# relay-set-d-latch.net
KiCad netlist of a schematic drawn in EAGLE
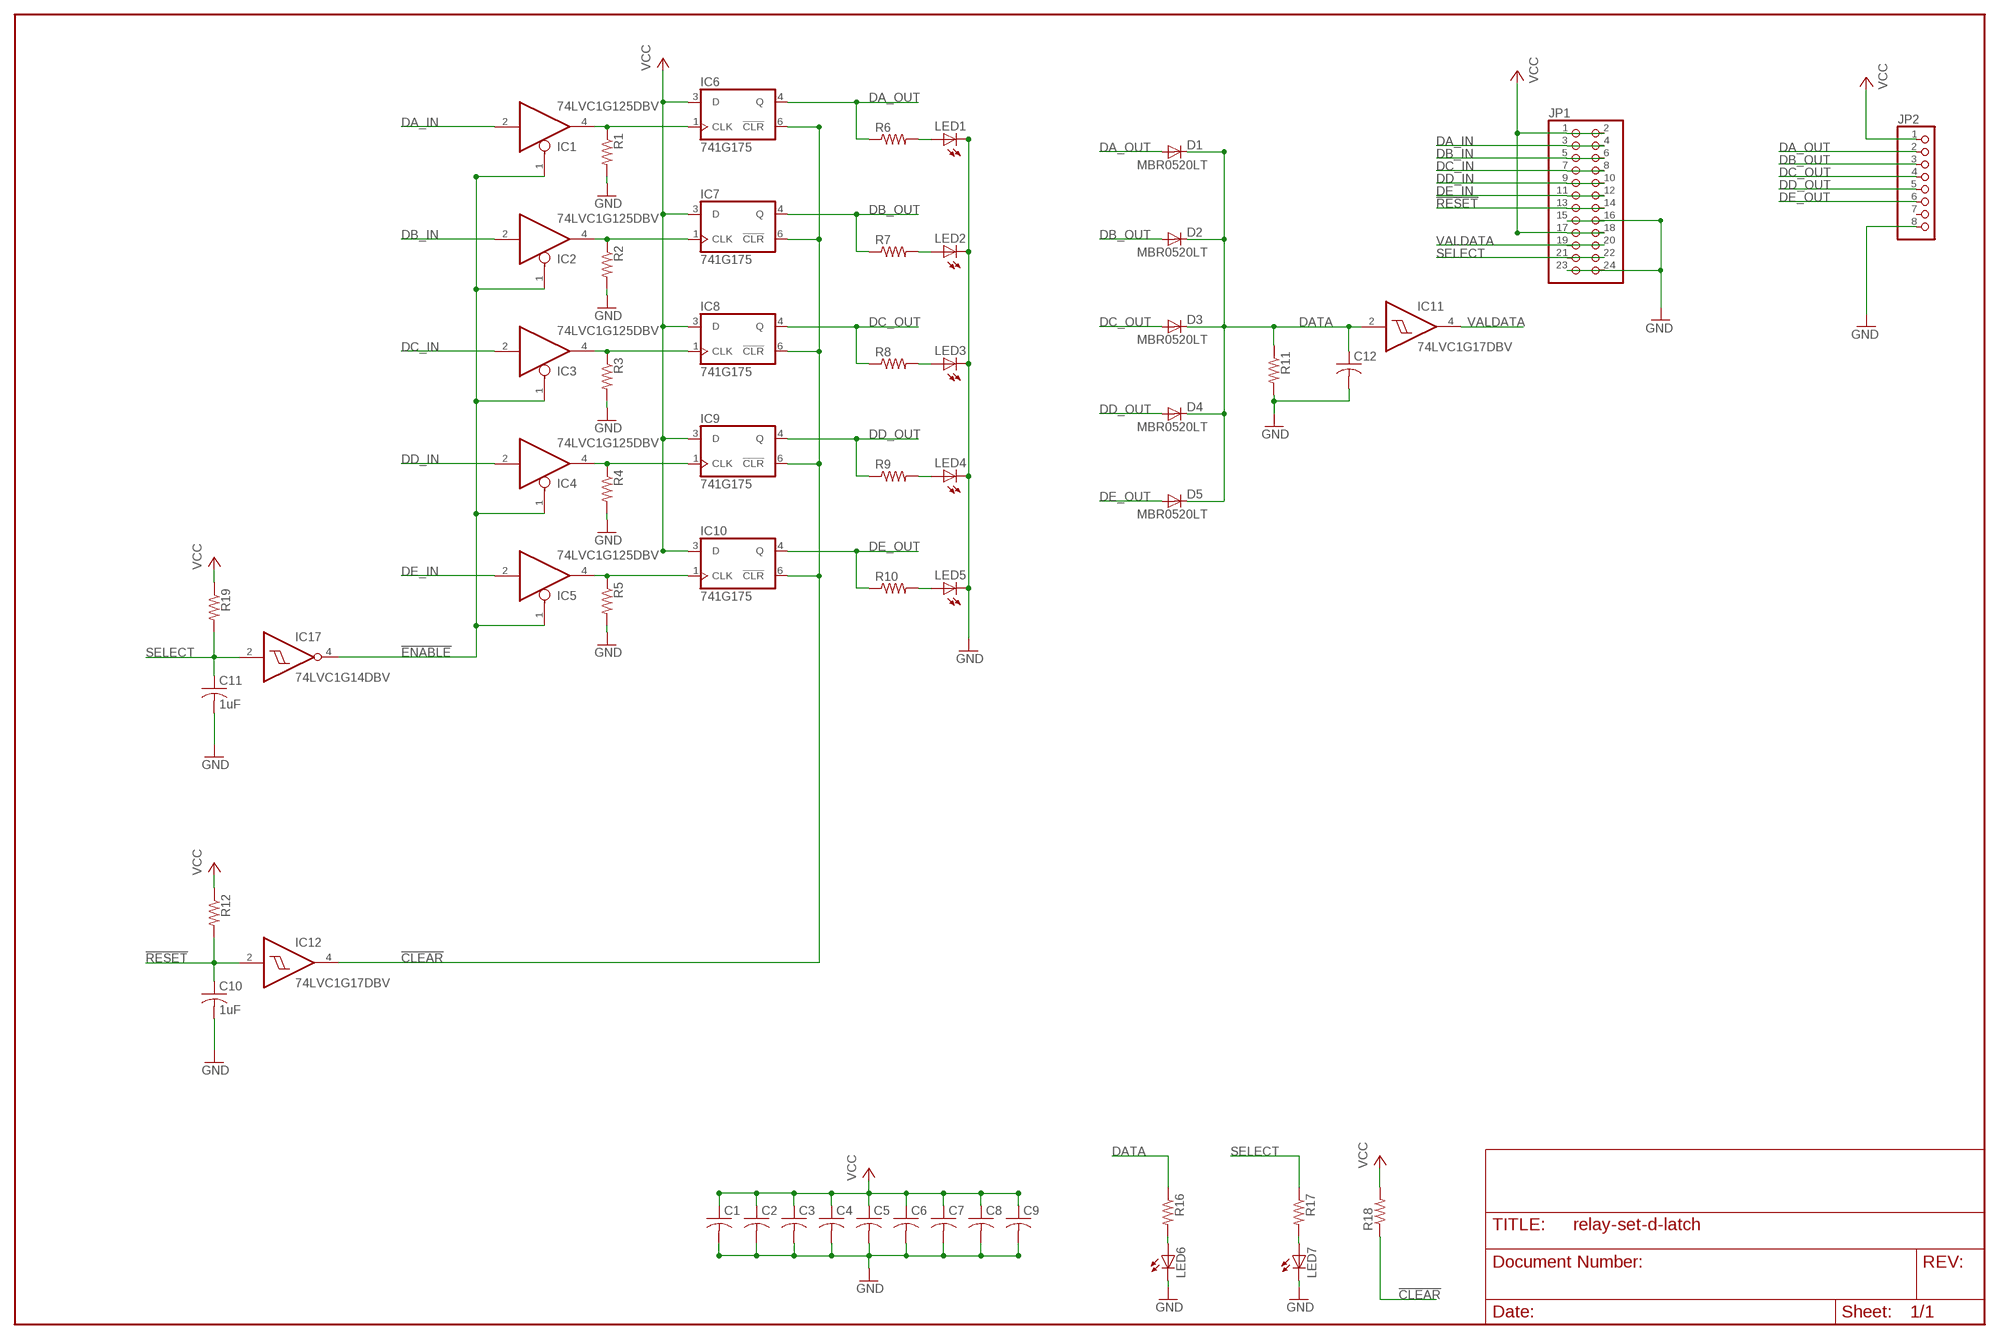
[diagram p0: schematic, sheet 1]

(export (version "E")
  (design (tool "Eeschema 10.0.6"))
  (components
    (comp (ref "C1")
      (value "C-USC0805")
      (footprint "eagle-import:C0805")
      (libsource (lib "eagle-import") (part "C-USC0805"))
    )
    (comp (ref "C2")
      (value "C-USC0805")
      (footprint "eagle-import:C0805")
      (libsource (lib "eagle-import") (part "C-USC0805"))
    )
    (comp (ref "C3")
      (value "C-USC0805")
      (footprint "eagle-import:C0805")
      (libsource (lib "eagle-import") (part "C-USC0805"))
    )
    (comp (ref "C4")
      (value "C-USC0805")
      (footprint "eagle-import:C0805")
      (libsource (lib "eagle-import") (part "C-USC0805"))
    )
    (comp (ref "C5")
      (value "C-USC0603K")
      (footprint "eagle-import:C0603K")
      (libsource (lib "eagle-import") (part "C-USC0603K"))
    )
    (comp (ref "C6")
      (value "C-USC0603K")
      (footprint "eagle-import:C0603K")
      (libsource (lib "eagle-import") (part "C-USC0603K"))
    )
    (comp (ref "C7")
      (value "C-USC0603K")
      (footprint "eagle-import:C0603K")
      (libsource (lib "eagle-import") (part "C-USC0603K"))
    )
    (comp (ref "C8")
      (value "C-USC0603K")
      (footprint "eagle-import:C0603K")
      (libsource (lib "eagle-import") (part "C-USC0603K"))
    )
    (comp (ref "C9")
      (value "C-USC0603K")
      (footprint "eagle-import:C0603K")
      (libsource (lib "eagle-import") (part "C-USC0603K"))
    )
    (comp (ref "C10")
      (value "1uF")
      (footprint "eagle-import:C0603K")
      (libsource (lib "eagle-import") (part "C-USC0603K"))
    )
    (comp (ref "C11")
      (value "1uF")
      (footprint "eagle-import:C0603K")
      (libsource (lib "eagle-import") (part "C-USC0603K"))
    )
    (comp (ref "C12")
      (value "C-USC0805")
      (footprint "eagle-import:C0805")
      (libsource (lib "eagle-import") (part "C-USC0805"))
    )
    (comp (ref "D1")
      (value "MBR0520LT")
      (footprint "eagle-import:SOD123")
      (libsource (lib "eagle-import") (part "MBR0520LT"))
    )
    (comp (ref "D2")
      (value "MBR0520LT")
      (footprint "eagle-import:SOD123")
      (libsource (lib "eagle-import") (part "MBR0520LT"))
    )
    (comp (ref "D3")
      (value "MBR0520LT")
      (footprint "eagle-import:SOD123")
      (libsource (lib "eagle-import") (part "MBR0520LT"))
    )
    (comp (ref "D4")
      (value "MBR0520LT")
      (footprint "eagle-import:SOD123")
      (libsource (lib "eagle-import") (part "MBR0520LT"))
    )
    (comp (ref "D5")
      (value "MBR0520LT")
      (footprint "eagle-import:SOD123")
      (libsource (lib "eagle-import") (part "MBR0520LT"))
    )
    (comp (ref "IC1")
      (value "74LVC1G125DBV")
      (footprint "eagle-import:SOT23-5")
      (libsource (lib "eagle-import") (part "741G125DBVLVC"))
    )
    (comp (ref "IC2")
      (value "74LVC1G125DBV")
      (footprint "eagle-import:SOT23-5")
      (libsource (lib "eagle-import") (part "741G125DBVLVC"))
    )
    (comp (ref "IC3")
      (value "74LVC1G125DBV")
      (footprint "eagle-import:SOT23-5")
      (libsource (lib "eagle-import") (part "741G125DBVLVC"))
    )
    (comp (ref "IC4")
      (value "74LVC1G125DBV")
      (footprint "eagle-import:SOT23-5")
      (libsource (lib "eagle-import") (part "741G125DBVLVC"))
    )
    (comp (ref "IC5")
      (value "74LVC1G125DBV")
      (footprint "eagle-import:SOT23-5")
      (libsource (lib "eagle-import") (part "741G125DBVLVC"))
    )
    (comp (ref "IC6")
      (value "741G175")
      (footprint "eagle-import:DBV_R-PDSO-G6")
      (libsource (lib "eagle-import") (part "741G175"))
    )
    (comp (ref "IC7")
      (value "741G175")
      (footprint "eagle-import:DBV_R-PDSO-G6")
      (libsource (lib "eagle-import") (part "741G175"))
    )
    (comp (ref "IC8")
      (value "741G175")
      (footprint "eagle-import:DBV_R-PDSO-G6")
      (libsource (lib "eagle-import") (part "741G175"))
    )
    (comp (ref "IC9")
      (value "741G175")
      (footprint "eagle-import:DBV_R-PDSO-G6")
      (libsource (lib "eagle-import") (part "741G175"))
    )
    (comp (ref "IC10")
      (value "741G175")
      (footprint "eagle-import:DBV_R-PDSO-G6")
      (libsource (lib "eagle-import") (part "741G175"))
    )
    (comp (ref "IC11")
      (value "74LVC1G17DBV")
      (footprint "eagle-import:SOT23-5")
      (libsource (lib "eagle-import") (part "741G17DBVLVC"))
    )
    (comp (ref "IC12")
      (value "74LVC1G17DBV")
      (footprint "eagle-import:SOT23-5")
      (libsource (lib "eagle-import") (part "741G17DBVLVC"))
    )
    (comp (ref "IC17")
      (value "74LVC1G14DBV")
      (footprint "eagle-import:SOT23-5")
      (libsource (lib "eagle-import") (part "741G14DBVLVC"))
    )
    (comp (ref "JP1")
      (value "PINHD-2X12")
      (footprint "eagle-import:2X12")
      (libsource (lib "eagle-import") (part "PINHD-2X12"))
    )
    (comp (ref "JP2")
      (value "PINHD-1X8")
      (footprint "eagle-import:1X08")
      (libsource (lib "eagle-import") (part "PINHD-1X8"))
    )
    (comp (ref "LED1")
      (value "LEDCHIP-LED0805")
      (footprint "eagle-import:CHIP-LED0805")
      (libsource (lib "eagle-import") (part "LEDCHIP-LED0805"))
    )
    (comp (ref "LED2")
      (value "LEDCHIP-LED0805")
      (footprint "eagle-import:CHIP-LED0805")
      (libsource (lib "eagle-import") (part "LEDCHIP-LED0805"))
    )
    (comp (ref "LED3")
      (value "LEDCHIP-LED0805")
      (footprint "eagle-import:CHIP-LED0805")
      (libsource (lib "eagle-import") (part "LEDCHIP-LED0805"))
    )
    (comp (ref "LED4")
      (value "LEDCHIP-LED0805")
      (footprint "eagle-import:CHIP-LED0805")
      (libsource (lib "eagle-import") (part "LEDCHIP-LED0805"))
    )
    (comp (ref "LED5")
      (value "LEDCHIP-LED0805")
      (footprint "eagle-import:CHIP-LED0805")
      (libsource (lib "eagle-import") (part "LEDCHIP-LED0805"))
    )
    (comp (ref "LED6")
      (value "LEDCHIP-LED0805")
      (footprint "eagle-import:CHIP-LED0805")
      (libsource (lib "eagle-import") (part "LEDCHIP-LED0805"))
    )
    (comp (ref "LED7")
      (value "LEDCHIP-LED0805")
      (footprint "eagle-import:CHIP-LED0805")
      (libsource (lib "eagle-import") (part "LEDCHIP-LED0805"))
    )
    (comp (ref "R1")
      (value "R-US_R0805")
      (footprint "eagle-import:R0805")
      (libsource (lib "eagle-import") (part "R-US_R0805"))
    )
    (comp (ref "R2")
      (value "R-US_R0805")
      (footprint "eagle-import:R0805")
      (libsource (lib "eagle-import") (part "R-US_R0805"))
    )
    (comp (ref "R3")
      (value "R-US_R0805")
      (footprint "eagle-import:R0805")
      (libsource (lib "eagle-import") (part "R-US_R0805"))
    )
    (comp (ref "R4")
      (value "R-US_R0805")
      (footprint "eagle-import:R0805")
      (libsource (lib "eagle-import") (part "R-US_R0805"))
    )
    (comp (ref "R5")
      (value "R-US_R0805")
      (footprint "eagle-import:R0805")
      (libsource (lib "eagle-import") (part "R-US_R0805"))
    )
    (comp (ref "R6")
      (value "R-US_R0805")
      (footprint "eagle-import:R0805")
      (libsource (lib "eagle-import") (part "R-US_R0805"))
    )
    (comp (ref "R7")
      (value "R-US_R0805")
      (footprint "eagle-import:R0805")
      (libsource (lib "eagle-import") (part "R-US_R0805"))
    )
    (comp (ref "R8")
      (value "R-US_R0805")
      (footprint "eagle-import:R0805")
      (libsource (lib "eagle-import") (part "R-US_R0805"))
    )
    (comp (ref "R9")
      (value "R-US_R0805")
      (footprint "eagle-import:R0805")
      (libsource (lib "eagle-import") (part "R-US_R0805"))
    )
    (comp (ref "R10")
      (value "R-US_R0805")
      (footprint "eagle-import:R0805")
      (libsource (lib "eagle-import") (part "R-US_R0805"))
    )
    (comp (ref "R11")
      (value "R-US_R0805")
      (footprint "eagle-import:R0805")
      (libsource (lib "eagle-import") (part "R-US_R0805"))
    )
    (comp (ref "R12")
      (value "R-US_R0805")
      (footprint "eagle-import:R0805")
      (libsource (lib "eagle-import") (part "R-US_R0805"))
    )
    (comp (ref "R16")
      (value "R-US_R0805")
      (footprint "eagle-import:R0805")
      (libsource (lib "eagle-import") (part "R-US_R0805"))
    )
    (comp (ref "R17")
      (value "R-US_R0805")
      (footprint "eagle-import:R0805")
      (libsource (lib "eagle-import") (part "R-US_R0805"))
    )
    (comp (ref "R18")
      (value "R-US_R0805")
      (footprint "eagle-import:R0805")
      (libsource (lib "eagle-import") (part "R-US_R0805"))
    )
    (comp (ref "R19")
      (value "R-US_R0805")
      (footprint "eagle-import:R0805")
      (libsource (lib "eagle-import") (part "R-US_R0805"))
    )
  )
  (nets
    (net (code "1") (name "/DATA") (class "Default")
      (node (ref "C12") (pin "1") (pinfunction "1_1") (pintype "passive"))
      (node (ref "D1") (pin "C") (pinfunction "C_C") (pintype "passive"))
      (node (ref "D2") (pin "C") (pinfunction "C_C") (pintype "passive"))
      (node (ref "D3") (pin "C") (pinfunction "C_C") (pintype "passive"))
      (node (ref "D4") (pin "C") (pinfunction "C_C") (pintype "passive"))
      (node (ref "D5") (pin "C") (pinfunction "C_C") (pintype "passive"))
      (node (ref "IC11") (pin "2") (pinfunction "I_2") (pintype "input"))
      (node (ref "R11") (pin "1") (pinfunction "1_1") (pintype "passive"))
      (node (ref "R16") (pin "1") (pinfunction "1_1") (pintype "passive"))
    )
    (net (code "2") (name "/DA_IN") (class "Default")
      (node (ref "IC1") (pin "2") (pinfunction "I_2") (pintype "input"))
      (node (ref "JP1") (pin "3") (pinfunction "3_3") (pintype "passive"))
      (node (ref "JP1") (pin "4") (pinfunction "4_4") (pintype "passive"))
    )
    (net (code "3") (name "/DA_OUT") (class "Default")
      (node (ref "D1") (pin "A") (pinfunction "A_A") (pintype "passive"))
      (node (ref "IC6") (pin "4") (pinfunction "Q_4") (pintype "output"))
      (node (ref "JP2") (pin "2") (pinfunction "2_2") (pintype "passive"))
      (node (ref "R6") (pin "1") (pinfunction "1_1") (pintype "passive"))
    )
    (net (code "4") (name "/DB_IN") (class "Default")
      (node (ref "IC2") (pin "2") (pinfunction "I_2") (pintype "input"))
      (node (ref "JP1") (pin "5") (pinfunction "5_5") (pintype "passive"))
      (node (ref "JP1") (pin "6") (pinfunction "6_6") (pintype "passive"))
    )
    (net (code "5") (name "/DB_OUT") (class "Default")
      (node (ref "D2") (pin "A") (pinfunction "A_A") (pintype "passive"))
      (node (ref "IC7") (pin "4") (pinfunction "Q_4") (pintype "output"))
      (node (ref "JP2") (pin "3") (pinfunction "3_3") (pintype "passive"))
      (node (ref "R7") (pin "1") (pinfunction "1_1") (pintype "passive"))
    )
    (net (code "6") (name "/DC_IN") (class "Default")
      (node (ref "IC3") (pin "2") (pinfunction "I_2") (pintype "input"))
      (node (ref "JP1") (pin "7") (pinfunction "7_7") (pintype "passive"))
      (node (ref "JP1") (pin "8") (pinfunction "8_8") (pintype "passive"))
    )
    (net (code "7") (name "/DC_OUT") (class "Default")
      (node (ref "D3") (pin "A") (pinfunction "A_A") (pintype "passive"))
      (node (ref "IC8") (pin "4") (pinfunction "Q_4") (pintype "output"))
      (node (ref "JP2") (pin "4") (pinfunction "4_4") (pintype "passive"))
      (node (ref "R8") (pin "1") (pinfunction "1_1") (pintype "passive"))
    )
    (net (code "8") (name "/DD_IN") (class "Default")
      (node (ref "IC4") (pin "2") (pinfunction "I_2") (pintype "input"))
      (node (ref "JP1") (pin "10") (pinfunction "10_10") (pintype "passive"))
      (node (ref "JP1") (pin "9") (pinfunction "9_9") (pintype "passive"))
    )
    (net (code "9") (name "/DD_OUT") (class "Default")
      (node (ref "D4") (pin "A") (pinfunction "A_A") (pintype "passive"))
      (node (ref "IC9") (pin "4") (pinfunction "Q_4") (pintype "output"))
      (node (ref "JP2") (pin "5") (pinfunction "5_5") (pintype "passive"))
      (node (ref "R9") (pin "1") (pinfunction "1_1") (pintype "passive"))
    )
    (net (code "10") (name "/DE_IN") (class "Default")
      (node (ref "IC5") (pin "2") (pinfunction "I_2") (pintype "input"))
      (node (ref "JP1") (pin "11") (pinfunction "11_11") (pintype "passive"))
      (node (ref "JP1") (pin "12") (pinfunction "12_12") (pintype "passive"))
    )
    (net (code "11") (name "/DE_OUT") (class "Default")
      (node (ref "D5") (pin "A") (pinfunction "A_A") (pintype "passive"))
      (node (ref "IC10") (pin "4") (pinfunction "Q_4") (pintype "output"))
      (node (ref "JP2") (pin "6") (pinfunction "6_6") (pintype "passive"))
      (node (ref "R10") (pin "1") (pinfunction "1_1") (pintype "passive"))
    )
    (net (code "12") (name "/SELECT") (class "Default")
      (node (ref "C11") (pin "1") (pinfunction "1_1") (pintype "passive"))
      (node (ref "IC17") (pin "2") (pinfunction "I_2") (pintype "input"))
      (node (ref "JP1") (pin "21") (pinfunction "21_21") (pintype "passive"))
      (node (ref "JP1") (pin "22") (pinfunction "22_22") (pintype "passive"))
      (node (ref "R17") (pin "1") (pinfunction "1_1") (pintype "passive"))
      (node (ref "R19") (pin "2") (pinfunction "2_2") (pintype "passive"))
    )
    (net (code "13") (name "/VALDATA") (class "Default")
      (node (ref "IC11") (pin "4") (pinfunction "O_4") (pintype "output"))
      (node (ref "JP1") (pin "19") (pinfunction "19_19") (pintype "passive"))
      (node (ref "JP1") (pin "20") (pinfunction "20_20") (pintype "passive"))
    )
    (net (code "14") (name "/~{CLEAR}") (class "Default")
      (node (ref "IC10") (pin "6") (pinfunction "~{CLR}_6") (pintype "output"))
      (node (ref "IC12") (pin "4") (pinfunction "O_4") (pintype "output"))
      (node (ref "IC6") (pin "6") (pinfunction "~{CLR}_6") (pintype "output"))
      (node (ref "IC7") (pin "6") (pinfunction "~{CLR}_6") (pintype "output"))
      (node (ref "IC8") (pin "6") (pinfunction "~{CLR}_6") (pintype "output"))
      (node (ref "IC9") (pin "6") (pinfunction "~{CLR}_6") (pintype "output"))
      (node (ref "R18") (pin "1") (pinfunction "1_1") (pintype "passive"))
    )
    (net (code "15") (name "/~{ENABLE}") (class "Default")
      (node (ref "IC1") (pin "1") (pinfunction "OE_1") (pintype "input"))
      (node (ref "IC17") (pin "4") (pinfunction "O_4") (pintype "output"))
      (node (ref "IC2") (pin "1") (pinfunction "OE_1") (pintype "input"))
      (node (ref "IC3") (pin "1") (pinfunction "OE_1") (pintype "input"))
      (node (ref "IC4") (pin "1") (pinfunction "OE_1") (pintype "input"))
      (node (ref "IC5") (pin "1") (pinfunction "OE_1") (pintype "input"))
    )
    (net (code "16") (name "/~{RESET}") (class "Default")
      (node (ref "C10") (pin "1") (pinfunction "1_1") (pintype "passive"))
      (node (ref "IC12") (pin "2") (pinfunction "I_2") (pintype "input"))
      (node (ref "JP1") (pin "13") (pinfunction "13_13") (pintype "passive"))
      (node (ref "JP1") (pin "14") (pinfunction "14_14") (pintype "passive"))
      (node (ref "R12") (pin "2") (pinfunction "2_2") (pintype "passive"))
    )
    (net (code "17") (name "GND") (class "Default")
      (node (ref "C1") (pin "2") (pinfunction "2_2") (pintype "passive"))
      (node (ref "C10") (pin "2") (pinfunction "2_2") (pintype "passive"))
      (node (ref "C11") (pin "2") (pinfunction "2_2") (pintype "passive"))
      (node (ref "C12") (pin "2") (pinfunction "2_2") (pintype "passive"))
      (node (ref "C2") (pin "2") (pinfunction "2_2") (pintype "passive"))
      (node (ref "C3") (pin "2") (pinfunction "2_2") (pintype "passive"))
      (node (ref "C4") (pin "2") (pinfunction "2_2") (pintype "passive"))
      (node (ref "C5") (pin "2") (pinfunction "2_2") (pintype "passive"))
      (node (ref "C6") (pin "2") (pinfunction "2_2") (pintype "passive"))
      (node (ref "C7") (pin "2") (pinfunction "2_2") (pintype "passive"))
      (node (ref "C8") (pin "2") (pinfunction "2_2") (pintype "passive"))
      (node (ref "C9") (pin "2") (pinfunction "2_2") (pintype "passive"))
      (node (ref "JP1") (pin "15") (pinfunction "15_15") (pintype "passive"))
      (node (ref "JP1") (pin "16") (pinfunction "16_16") (pintype "passive"))
      (node (ref "JP1") (pin "23") (pinfunction "23_23") (pintype "passive"))
      (node (ref "JP1") (pin "24") (pinfunction "24_24") (pintype "passive"))
      (node (ref "JP2") (pin "8") (pinfunction "8_8") (pintype "passive"))
      (node (ref "LED1") (pin "C") (pinfunction "C_C") (pintype "passive"))
      (node (ref "LED2") (pin "C") (pinfunction "C_C") (pintype "passive"))
      (node (ref "LED3") (pin "C") (pinfunction "C_C") (pintype "passive"))
      (node (ref "LED4") (pin "C") (pinfunction "C_C") (pintype "passive"))
      (node (ref "LED5") (pin "C") (pinfunction "C_C") (pintype "passive"))
      (node (ref "LED6") (pin "C") (pinfunction "C_C") (pintype "passive"))
      (node (ref "LED7") (pin "C") (pinfunction "C_C") (pintype "passive"))
      (node (ref "R1") (pin "2") (pinfunction "2_2") (pintype "passive"))
      (node (ref "R11") (pin "2") (pinfunction "2_2") (pintype "passive"))
      (node (ref "R2") (pin "2") (pinfunction "2_2") (pintype "passive"))
      (node (ref "R3") (pin "2") (pinfunction "2_2") (pintype "passive"))
      (node (ref "R4") (pin "2") (pinfunction "2_2") (pintype "passive"))
      (node (ref "R5") (pin "2") (pinfunction "2_2") (pintype "passive"))
    )
    (net (code "18") (name "Net-(IC1A-O)") (class "Default")
      (node (ref "IC1") (pin "4") (pinfunction "O_4") (pintype "tri_state"))
      (node (ref "IC6") (pin "1") (pinfunction "CLK_1") (pintype "input"))
      (node (ref "R1") (pin "1") (pinfunction "1_1") (pintype "passive"))
    )
    (net (code "19") (name "Net-(IC2A-O)") (class "Default")
      (node (ref "IC2") (pin "4") (pinfunction "O_4") (pintype "tri_state"))
      (node (ref "IC7") (pin "1") (pinfunction "CLK_1") (pintype "input"))
      (node (ref "R2") (pin "1") (pinfunction "1_1") (pintype "passive"))
    )
    (net (code "20") (name "Net-(IC3A-O)") (class "Default")
      (node (ref "IC3") (pin "4") (pinfunction "O_4") (pintype "tri_state"))
      (node (ref "IC8") (pin "1") (pinfunction "CLK_1") (pintype "input"))
      (node (ref "R3") (pin "1") (pinfunction "1_1") (pintype "passive"))
    )
    (net (code "21") (name "Net-(IC4A-O)") (class "Default")
      (node (ref "IC4") (pin "4") (pinfunction "O_4") (pintype "tri_state"))
      (node (ref "IC9") (pin "1") (pinfunction "CLK_1") (pintype "input"))
      (node (ref "R4") (pin "1") (pinfunction "1_1") (pintype "passive"))
    )
    (net (code "22") (name "Net-(IC10A-CLK)") (class "Default")
      (node (ref "IC10") (pin "1") (pinfunction "CLK_1") (pintype "input"))
      (node (ref "IC5") (pin "4") (pinfunction "O_4") (pintype "tri_state"))
      (node (ref "R5") (pin "1") (pinfunction "1_1") (pintype "passive"))
    )
    (net (code "23") (name "Net-(LED1-PadA)") (class "Default")
      (node (ref "LED1") (pin "A") (pinfunction "A_A") (pintype "passive"))
      (node (ref "R6") (pin "2") (pinfunction "2_2") (pintype "passive"))
    )
    (net (code "24") (name "Net-(LED2-PadA)") (class "Default")
      (node (ref "LED2") (pin "A") (pinfunction "A_A") (pintype "passive"))
      (node (ref "R7") (pin "2") (pinfunction "2_2") (pintype "passive"))
    )
    (net (code "25") (name "Net-(LED3-PadA)") (class "Default")
      (node (ref "LED3") (pin "A") (pinfunction "A_A") (pintype "passive"))
      (node (ref "R8") (pin "2") (pinfunction "2_2") (pintype "passive"))
    )
    (net (code "26") (name "Net-(LED4-PadA)") (class "Default")
      (node (ref "LED4") (pin "A") (pinfunction "A_A") (pintype "passive"))
      (node (ref "R9") (pin "2") (pinfunction "2_2") (pintype "passive"))
    )
    (net (code "27") (name "Net-(LED5-PadA)") (class "Default")
      (node (ref "LED5") (pin "A") (pinfunction "A_A") (pintype "passive"))
      (node (ref "R10") (pin "2") (pinfunction "2_2") (pintype "passive"))
    )
    (net (code "28") (name "Net-(LED6-PadA)") (class "Default")
      (node (ref "LED6") (pin "A") (pinfunction "A_A") (pintype "passive"))
      (node (ref "R16") (pin "2") (pinfunction "2_2") (pintype "passive"))
    )
    (net (code "29") (name "Net-(LED7-PadA)") (class "Default")
      (node (ref "LED7") (pin "A") (pinfunction "A_A") (pintype "passive"))
      (node (ref "R17") (pin "2") (pinfunction "2_2") (pintype "passive"))
    )
    (net (code "30") (name "VCC") (class "Default")
      (node (ref "C1") (pin "1") (pinfunction "1_1") (pintype "passive"))
      (node (ref "C2") (pin "1") (pinfunction "1_1") (pintype "passive"))
      (node (ref "C3") (pin "1") (pinfunction "1_1") (pintype "passive"))
      (node (ref "C4") (pin "1") (pinfunction "1_1") (pintype "passive"))
      (node (ref "C5") (pin "1") (pinfunction "1_1") (pintype "passive"))
      (node (ref "C6") (pin "1") (pinfunction "1_1") (pintype "passive"))
      (node (ref "C7") (pin "1") (pinfunction "1_1") (pintype "passive"))
      (node (ref "C8") (pin "1") (pinfunction "1_1") (pintype "passive"))
      (node (ref "C9") (pin "1") (pinfunction "1_1") (pintype "passive"))
      (node (ref "IC10") (pin "3") (pinfunction "D_3") (pintype "input"))
      (node (ref "IC6") (pin "3") (pinfunction "D_3") (pintype "input"))
      (node (ref "IC7") (pin "3") (pinfunction "D_3") (pintype "input"))
      (node (ref "IC8") (pin "3") (pinfunction "D_3") (pintype "input"))
      (node (ref "IC9") (pin "3") (pinfunction "D_3") (pintype "input"))
      (node (ref "JP1") (pin "1") (pinfunction "1_1") (pintype "passive"))
      (node (ref "JP1") (pin "17") (pinfunction "17_17") (pintype "passive"))
      (node (ref "JP1") (pin "18") (pinfunction "18_18") (pintype "passive"))
      (node (ref "JP1") (pin "2") (pinfunction "2_2") (pintype "passive"))
      (node (ref "JP2") (pin "1") (pinfunction "1_1") (pintype "passive"))
      (node (ref "R12") (pin "1") (pinfunction "1_1") (pintype "passive"))
      (node (ref "R18") (pin "2") (pinfunction "2_2") (pintype "passive"))
      (node (ref "R19") (pin "1") (pinfunction "1_1") (pintype "passive"))
    )
    (net (code "31") (name "unconnected-(JP2-Pad7)") (class "Default")
      (node (ref "JP2") (pin "7") (pinfunction "7_7") (pintype "passive"))
    )
  )
)
